# PSU_1084SET_1V8.net
KiCad netlist of a schematic drawn in Altium Designer
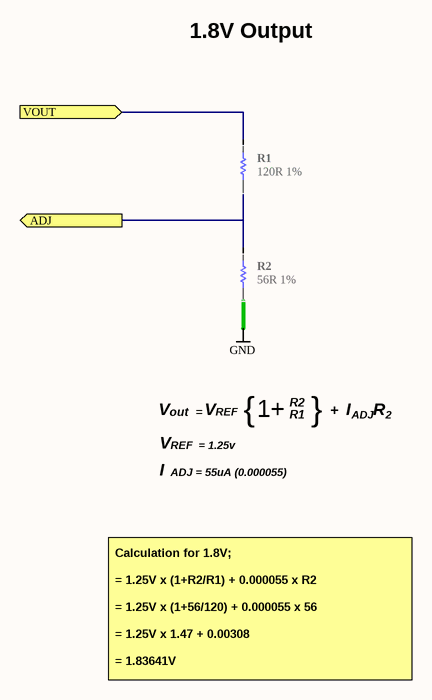
[diagram p0: PSU_1084SET_1V8.SchDoc]

(export (version "E")
  (design (tool "Eeschema 10.0.6"))
  (components
    (comp (ref "R1")
      (value "120R 1%")
      (footprint "RESC1005-STAR")
      (description "Resistor, 120R 1% 0402 (1005)")
      (fields (field (name "TOLERANCE") "1 %"))
      (libsource (lib "AltiumDesignLibrary") (part "RES"))
    )
    (comp (ref "R2")
      (value "56R 1%")
      (footprint "RESC1005-STAR")
      (description "Resistor, 56R 1% 0402")
      (fields (field (name "TOLERANCE") "1 %"))
      (libsource (lib "AltiumDesignLibrary") (part "RES"))
    )
  )
  (nets
    (net (code "1") (name "/ADJ") (class "Default")
      (node (ref "R1") (pin "1") (pinfunction "1_1") (pintype "passive"))
      (node (ref "R2") (pin "1") (pinfunction "1_1") (pintype "passive"))
    )
    (net (code "2") (name "/VOUT") (class "Default")
      (node (ref "R1") (pin "2") (pinfunction "2_2") (pintype "passive"))
    )
    (net (code "3") (name "GND") (class "Default")
      (node (ref "R2") (pin "2") (pinfunction "2_2") (pintype "passive"))
    )
  )
)
